# ignition4.net
KiCad netlist of a schematic drawn in EAGLE
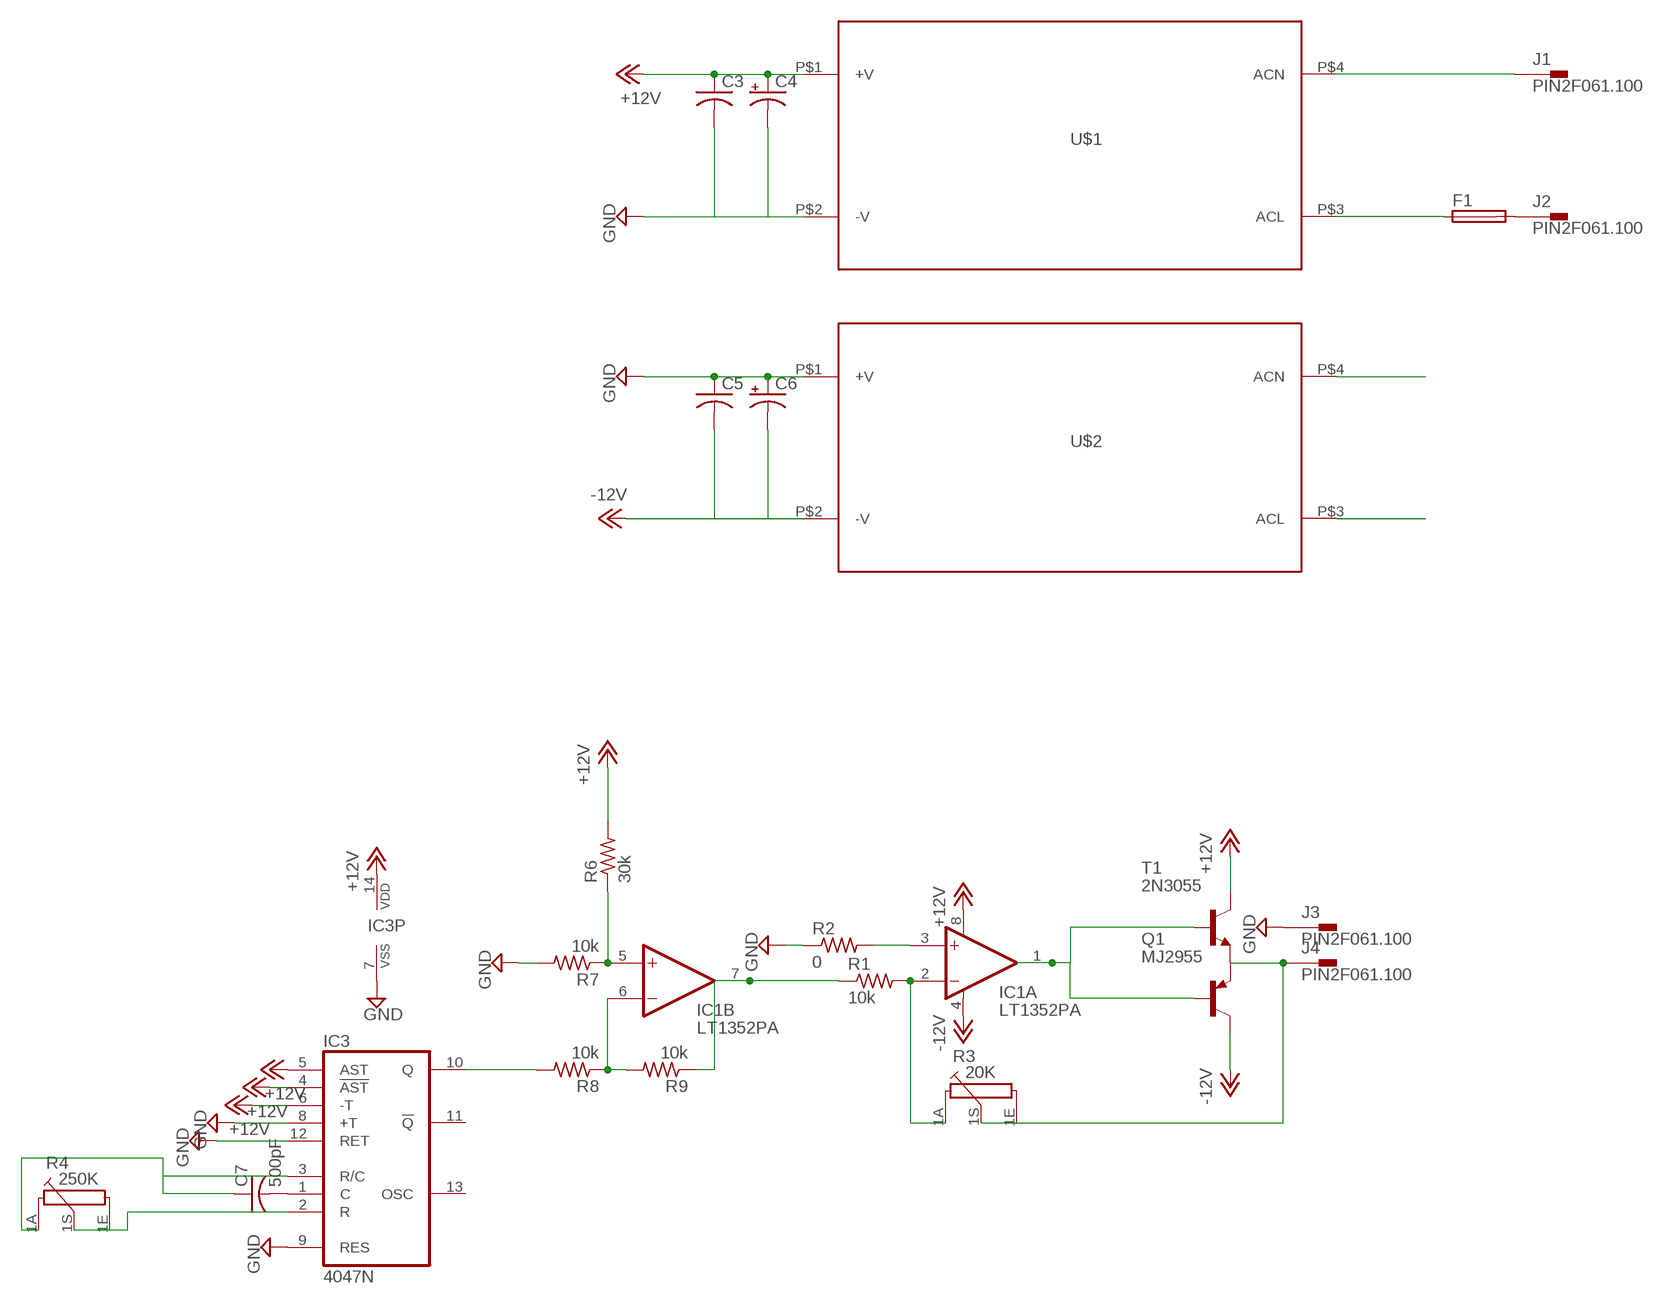
[diagram p0: schematic, sheet 1]

(export (version "E")
  (design (tool "Eeschema 10.0.6"))
  (components
    (comp (ref "C3")
      (value "C-US050-035X075")
      (footprint "eagle-import:C050-035X075")
      (libsource (lib "eagle-import") (part "C-US050-035X075"))
    )
    (comp (ref "C4")
      (value "CPOL-USE5-5")
      (footprint "eagle-import:E5-5")
      (libsource (lib "eagle-import") (part "CPOL-USE5-5"))
    )
    (comp (ref "C5")
      (value "C-US050-035X075")
      (footprint "eagle-import:C050-035X075")
      (libsource (lib "eagle-import") (part "C-US050-035X075"))
    )
    (comp (ref "C6")
      (value "CPOL-USE5-5")
      (footprint "eagle-import:E5-5")
      (libsource (lib "eagle-import") (part "CPOL-USE5-5"))
    )
    (comp (ref "C7")
      (value "500pF")
      (footprint "eagle-import:C075-042X103")
      (libsource (lib "eagle-import") (part "C-US075-042X103"))
    )
    (comp (ref "F1")
      (value "SH25")
      (footprint "eagle-import:SH25")
      (fields (field (name "MF") "SCHURTER") (field (name "MPN") "0031.8211"))
      (libsource (lib "eagle-import") (part "SH25"))
    )
    (comp (ref "IC1")
      (value "LT1352PA")
      (footprint "eagle-import:DIL08")
      (libsource (lib "eagle-import") (part "LT1352PA"))
    )
    (comp (ref "IC3")
      (value "4047N")
      (footprint "eagle-import:DIL14")
      (libsource (lib "eagle-import") (part "4047N"))
    )
    (comp (ref "J1")
      (value "PIN2F061.100")
      (footprint "eagle-import:F061.100")
      (libsource (lib "eagle-import") (part "PIN2F061.100"))
    )
    (comp (ref "J2")
      (value "PIN2F061.100")
      (footprint "eagle-import:F061.100")
      (libsource (lib "eagle-import") (part "PIN2F061.100"))
    )
    (comp (ref "J3")
      (value "PIN2F061.100")
      (footprint "eagle-import:F061.100")
      (libsource (lib "eagle-import") (part "PIN2F061.100"))
    )
    (comp (ref "J4")
      (value "PIN2F061.100")
      (footprint "eagle-import:F061.100")
      (libsource (lib "eagle-import") (part "PIN2F061.100"))
    )
    (comp (ref "Q1")
      (value "MJ2955")
      (footprint "eagle-import:TO3")
      (libsource (lib "eagle-import") (part "MJ2955"))
    )
    (comp (ref "R1")
      (value "10k")
      (footprint "eagle-import:0207_15")
      (libsource (lib "eagle-import") (part "R-US_0207/15"))
    )
    (comp (ref "R2")
      (value "0")
      (footprint "eagle-import:0207_15")
      (libsource (lib "eagle-import") (part "R-US_0207/15"))
    )
    (comp (ref "R3")
      (value "20K")
      (footprint "eagle-import:PC16S")
      (libsource (lib "eagle-import") (part "PC16S"))
    )
    (comp (ref "R4")
      (value "250K")
      (footprint "eagle-import:PC16S")
      (libsource (lib "eagle-import") (part "PC16S"))
    )
    (comp (ref "R6")
      (value "30k")
      (footprint "eagle-import:0207_12")
      (libsource (lib "eagle-import") (part "R-US_0207/12"))
    )
    (comp (ref "R7")
      (value "10k")
      (footprint "eagle-import:0207_10")
      (libsource (lib "eagle-import") (part "R-US_0207/10"))
    )
    (comp (ref "R8")
      (value "10k")
      (footprint "eagle-import:0207_10")
      (libsource (lib "eagle-import") (part "R-US_0207/10"))
    )
    (comp (ref "R9")
      (value "10k")
      (footprint "eagle-import:0207_10")
      (libsource (lib "eagle-import") (part "R-US_0207/10"))
    )
    (comp (ref "T1")
      (value "2N3055")
      (footprint "eagle-import:TO3")
      (libsource (lib "eagle-import") (part "2N3055"))
    )
    (comp (ref "U$1")
      (value "IRM-60-12")
      (footprint "eagle-import:IRM-60-12")
      (libsource (lib "eagle-import") (part "IRM-60-12"))
    )
    (comp (ref "U$2")
      (value "IRM-60-12")
      (footprint "eagle-import:IRM-60-12")
      (libsource (lib "eagle-import") (part "IRM-60-12"))
    )
  )
  (nets
    (net (code "1") (name "+12V") (class "Default")
      (node (ref "C3") (pin "1") (pinfunction "1_1") (pintype "passive"))
      (node (ref "C4") (pin "+") (pinfunction "+_+") (pintype "passive"))
      (node (ref "IC1") (pin "8") (pinfunction "V+_8") (pintype "power_in"))
      (node (ref "IC3") (pin "14") (pinfunction "VDD_14") (pintype "power_in"))
      (node (ref "IC3") (pin "4") (pinfunction "~{AST}_4") (pintype "input"))
      (node (ref "IC3") (pin "5") (pinfunction "AST_5") (pintype "input"))
      (node (ref "IC3") (pin "6") (pinfunction "-T_6") (pintype "input"))
      (node (ref "R6") (pin "2") (pinfunction "2_2") (pintype "passive"))
      (node (ref "T1") (pin "C") (pinfunction "C_C") (pintype "passive"))
      (node (ref "T1") (pin "C/") (pinfunction "C_C/") (pintype "passive"))
      (node (ref "U$1") (pin "P$1") (pinfunction "+V_P$1") (pintype "bidirectional"))
    )
    (net (code "2") (name "-12V") (class "Default")
      (node (ref "C5") (pin "2") (pinfunction "2_2") (pintype "passive"))
      (node (ref "C6") (pin "-") (pinfunction "-_-") (pintype "passive"))
      (node (ref "IC1") (pin "4") (pinfunction "V-_4") (pintype "power_in"))
      (node (ref "Q1") (pin "C") (pinfunction "C_C") (pintype "passive"))
      (node (ref "Q1") (pin "C/") (pinfunction "C_C/") (pintype "passive"))
      (node (ref "U$2") (pin "P$2") (pinfunction "-V_P$2") (pintype "bidirectional"))
    )
    (net (code "3") (name "/L") (class "Default")
      (node (ref "F1") (pin "1") (pinfunction "1_1") (pintype "passive"))
      (node (ref "U$1") (pin "P$3") (pinfunction "ACL_P$3") (pintype "bidirectional"))
      (node (ref "U$2") (pin "P$3") (pinfunction "ACL_P$3") (pintype "bidirectional"))
    )
    (net (code "4") (name "/N") (class "Default")
      (node (ref "J1") (pin "A1") (pinfunction "1_A1") (pintype "passive"))
      (node (ref "J1") (pin "A2") (pinfunction "1_A2") (pintype "passive"))
      (node (ref "U$1") (pin "P$4") (pinfunction "ACN_P$4") (pintype "bidirectional"))
      (node (ref "U$2") (pin "P$4") (pinfunction "ACN_P$4") (pintype "bidirectional"))
    )
    (net (code "5") (name "GND") (class "Default")
      (node (ref "C3") (pin "2") (pinfunction "2_2") (pintype "passive"))
      (node (ref "C4") (pin "-") (pinfunction "-_-") (pintype "passive"))
      (node (ref "C5") (pin "1") (pinfunction "1_1") (pintype "passive"))
      (node (ref "C6") (pin "+") (pinfunction "+_+") (pintype "passive"))
      (node (ref "IC3") (pin "12") (pinfunction "RET_12") (pintype "input"))
      (node (ref "IC3") (pin "7") (pinfunction "VSS_7") (pintype "power_in"))
      (node (ref "IC3") (pin "8") (pinfunction "+T_8") (pintype "input"))
      (node (ref "IC3") (pin "9") (pinfunction "RES_9") (pintype "input"))
      (node (ref "J3") (pin "A1") (pinfunction "1_A1") (pintype "passive"))
      (node (ref "J3") (pin "A2") (pinfunction "1_A2") (pintype "passive"))
      (node (ref "R2") (pin "1") (pinfunction "1_1") (pintype "passive"))
      (node (ref "R7") (pin "2") (pinfunction "2_2") (pintype "passive"))
      (node (ref "U$1") (pin "P$2") (pinfunction "-V_P$2") (pintype "bidirectional"))
      (node (ref "U$2") (pin "P$1") (pinfunction "+V_P$1") (pintype "bidirectional"))
    )
    (net (code "6") (name "Net-(F1-Pad2)") (class "Default")
      (node (ref "F1") (pin "2") (pinfunction "2_2") (pintype "passive"))
      (node (ref "J2") (pin "A1") (pinfunction "1_A1") (pintype "passive"))
      (node (ref "J2") (pin "A2") (pinfunction "1_A2") (pintype "passive"))
    )
    (net (code "7") (name "Net-(IC1A-+IN)") (class "Default")
      (node (ref "IC1") (pin "3") (pinfunction "+IN_3") (pintype "input"))
      (node (ref "R2") (pin "2") (pinfunction "2_2") (pintype "passive"))
    )
    (net (code "8") (name "Net-(IC1A--IN)") (class "Default")
      (node (ref "IC1") (pin "2") (pinfunction "-IN_2") (pintype "input"))
      (node (ref "R1") (pin "2") (pinfunction "2_2") (pintype "passive"))
      (node (ref "R3") (pin "1A") (pinfunction "1A_1A") (pintype "passive"))
    )
    (net (code "9") (name "Net-(IC1A-OUT)") (class "Default")
      (node (ref "IC1") (pin "1") (pinfunction "OUT_1") (pintype "output"))
      (node (ref "Q1") (pin "B") (pinfunction "B_B") (pintype "passive"))
      (node (ref "T1") (pin "B") (pinfunction "B_B") (pintype "passive"))
    )
    (net (code "10") (name "Net-(IC1B-+IN)") (class "Default")
      (node (ref "IC1") (pin "5") (pinfunction "+IN_5") (pintype "input"))
      (node (ref "R6") (pin "1") (pinfunction "1_1") (pintype "passive"))
      (node (ref "R7") (pin "1") (pinfunction "1_1") (pintype "passive"))
    )
    (net (code "11") (name "Net-(IC1B--IN)") (class "Default")
      (node (ref "IC1") (pin "6") (pinfunction "-IN_6") (pintype "input"))
      (node (ref "R8") (pin "1") (pinfunction "1_1") (pintype "passive"))
      (node (ref "R9") (pin "2") (pinfunction "2_2") (pintype "passive"))
    )
    (net (code "12") (name "Net-(IC1B-OUT)") (class "Default")
      (node (ref "IC1") (pin "7") (pinfunction "OUT_7") (pintype "output"))
      (node (ref "R1") (pin "1") (pinfunction "1_1") (pintype "passive"))
      (node (ref "R9") (pin "1") (pinfunction "1_1") (pintype "passive"))
    )
    (net (code "13") (name "Net-(IC3A-C)") (class "Default")
      (node (ref "C7") (pin "2") (pinfunction "2_2") (pintype "passive"))
      (node (ref "IC3") (pin "1") (pinfunction "C_1") (pintype "input"))
    )
    (net (code "14") (name "Net-(IC3A-Q)") (class "Default")
      (node (ref "IC3") (pin "10") (pinfunction "Q_10") (pintype "output"))
      (node (ref "R8") (pin "2") (pinfunction "2_2") (pintype "passive"))
    )
    (net (code "15") (name "Net-(IC3A-R)") (class "Default")
      (node (ref "IC3") (pin "2") (pinfunction "R_2") (pintype "input"))
      (node (ref "R4") (pin "1E") (pinfunction "1E_1E") (pintype "passive"))
      (node (ref "R4") (pin "1S") (pinfunction "1S_1S") (pintype "passive"))
    )
    (net (code "16") (name "Net-(IC3A-R{slash}C)") (class "Default")
      (node (ref "C7") (pin "1") (pinfunction "1_1") (pintype "passive"))
      (node (ref "IC3") (pin "3") (pinfunction "R/C_3") (pintype "input"))
      (node (ref "R4") (pin "1A") (pinfunction "1A_1A") (pintype "passive"))
    )
    (net (code "17") (name "Net-(J4-1-PadA1)") (class "Default")
      (node (ref "J4") (pin "A1") (pinfunction "1_A1") (pintype "passive"))
      (node (ref "J4") (pin "A2") (pinfunction "1_A2") (pintype "passive"))
      (node (ref "Q1") (pin "E") (pinfunction "E_E") (pintype "passive"))
      (node (ref "R3") (pin "1E") (pinfunction "1E_1E") (pintype "passive"))
      (node (ref "R3") (pin "1S") (pinfunction "1S_1S") (pintype "passive"))
      (node (ref "T1") (pin "E") (pinfunction "E_E") (pintype "passive"))
    )
    (net (code "18") (name "unconnected-(IC3A-OSC-Pad13)") (class "Default")
      (node (ref "IC3") (pin "13") (pinfunction "OSC_13") (pintype "output"))
    )
    (net (code "19") (name "unconnected-(IC3A-~{Q}-Pad11)") (class "Default")
      (node (ref "IC3") (pin "11") (pinfunction "~{Q}_11") (pintype "output"))
    )
  )
)
